# 1-Schematic_TFG-DALI.net
KiCad netlist of a schematic drawn in EasyEDA
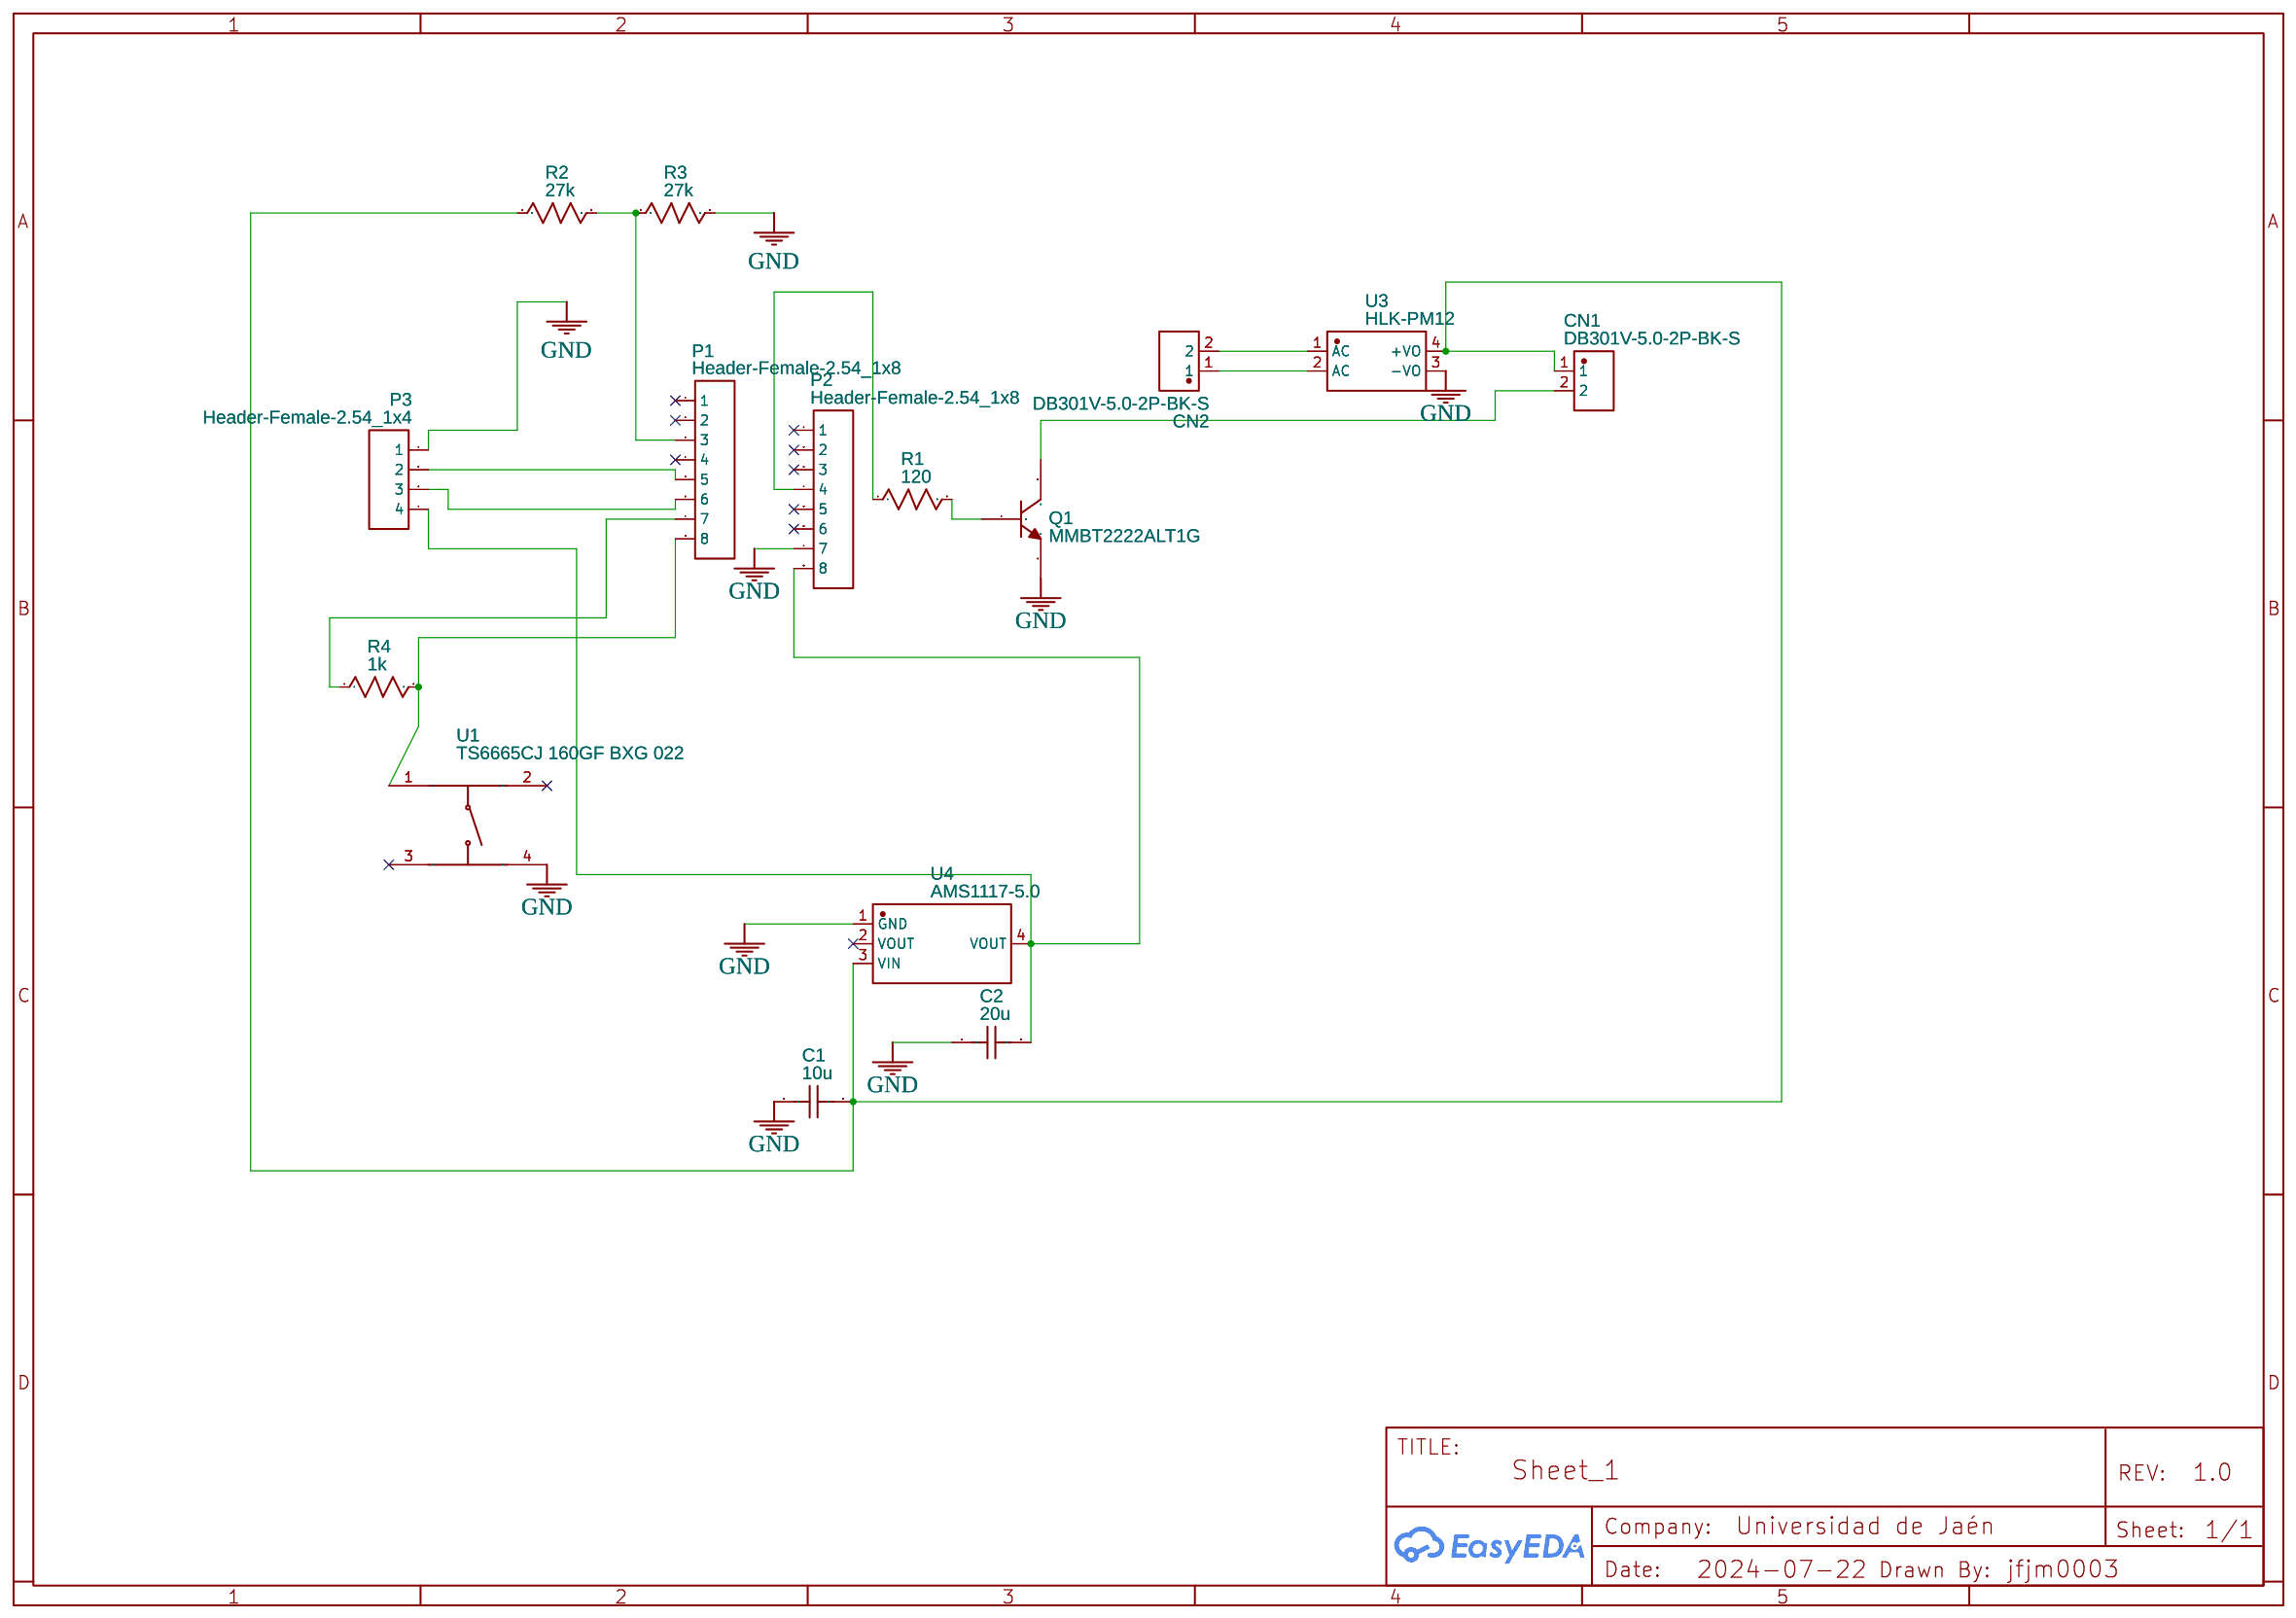
[diagram p0: schematic sheet]

(export (version "E")
  (design (tool "Eeschema 10.0.6"))
  (components
    (comp (ref "C1")
      (value "10u")
      (fields
        (field (name "Manufacturer Part") "CL31A106KBHNNNE")
        (field (name "Manufacturer") "SAMSUNG(三星)")
      )
      (libsource (lib "") (part "C_0603_US"))
    )
    (comp (ref "C2")
      (value "20u")
      (fields
        (field (name "Manufacturer Part") "GRMJN7R61C206ME05D")
        (field (name "Manufacturer") "muRata(村田)")
      )
      (libsource (lib "") (part "C_0603_US"))
    )
    (comp (ref "CN1")
      (value "DB301V-5.0-2P-BK-S")
      (fields (field (name "Manufacturer") "DORABO(地博电气)"))
      (libsource (lib "") (part "DB301V-5.0-2P-BK-S"))
    )
    (comp (ref "CN2")
      (value "DB301V-5.0-2P-BK-S")
      (fields (field (name "Manufacturer") "DORABO(地博电气)"))
      (libsource (lib "") (part "DB301V-5.0-2P-BK-S_1"))
    )
    (comp (ref "P1")
      (value "Header-Female-2.54_1x8")
      (fields (field (name "Manufacturer Part") "2.54-1*8P母环保") (field (name "Manufacturer") "BOOMELE(博穆精密)"))
      (libsource (lib "") (part "Header-Female-2.54_1x8"))
    )
    (comp (ref "P2")
      (value "Header-Female-2.54_1x8")
      (fields (field (name "Manufacturer Part") "2.54-1*8P母环保") (field (name "Manufacturer") "BOOMELE(博穆精密)"))
      (libsource (lib "") (part "Header-Female-2.54_1x8"))
    )
    (comp (ref "P3")
      (value "Header-Female-2.54_1x4")
      (fields (field (name "Manufacturer") "ReliaPro"))
      (libsource (lib "") (part "Header-Female-2.54_1x4"))
    )
    (comp (ref "Q1")
      (value "MMBT2222ALT1G")
      (fields (field (name "Manufacturer") "onsemi(安森美)"))
      (libsource (lib "") (part "MMBT2222ALT1G"))
    )
    (comp (ref "R1") (value "120") (libsource (lib "") (part "R_0603_US")))
    (comp (ref "R2") (value "27k") (libsource (lib "") (part "R_0603_US")))
    (comp (ref "R3") (value "27k") (libsource (lib "") (part "R_0603_US")))
    (comp (ref "R4") (value "1k") (libsource (lib "") (part "R_0603_US")))
    (comp (ref "U1")
      (value "TS6665CJ 160GF BXG 022")
      (fields
        (field (name "Manufacturer Part") "TS6665CJ 160gf BXG 022")
        (field (name "Manufacturer") "SHOU HAN(首韩)")
      )
      (libsource (lib "") (part "TS6665CJ 160GF BXG 022"))
    )
    (comp (ref "U3")
      (value "HLK-PM12")
      (fields (field (name "Manufacturer") "HI-LINK(海凌科)"))
      (libsource (lib "") (part "HLK-PM12"))
    )
    (comp (ref "U4")
      (value "AMS1117-5.0")
      (fields (field (name "Manufacturer") "AMS"))
      (libsource (lib "") (part "AMS1117-5.0"))
    )
  )
  (nets
    (net (code "1") (name "GND") (class "Default")
      (node (ref "C1") (pin "1") (pinfunction "1_1") (pintype "unspecified"))
      (node (ref "C2") (pin "1") (pinfunction "1_1") (pintype "unspecified"))
      (node (ref "P2") (pin "7") (pinfunction "7_7") (pintype "input"))
      (node (ref "P3") (pin "1") (pinfunction "1_1") (pintype "input"))
      (node (ref "Q1") (pin "2") (pinfunction "E_2") (pintype "unspecified"))
      (node (ref "R3") (pin "2") (pinfunction "2_2") (pintype "unspecified"))
      (node (ref "U1") (pin "4") (pinfunction "D_4") (pintype "unspecified"))
      (node (ref "U3") (pin "3") (pinfunction "-VO_3") (pintype "unspecified"))
      (node (ref "U4") (pin "1") (pinfunction "GND_1") (pintype "unspecified"))
    )
    (net (code "2") (name "Net-(C2-Pad2)") (class "Default")
      (node (ref "C2") (pin "2") (pinfunction "2_2") (pintype "unspecified"))
      (node (ref "P2") (pin "8") (pinfunction "8_8") (pintype "input"))
      (node (ref "P3") (pin "4") (pinfunction "4_4") (pintype "input"))
      (node (ref "U4") (pin "4") (pinfunction "VOUT_4") (pintype "unspecified"))
    )
    (net (code "3") (name "Net-(CN2-Pad1)") (class "Default")
      (node (ref "CN2") (pin "1") (pinfunction "1_1") (pintype "unspecified"))
      (node (ref "U3") (pin "2") (pinfunction "AC_2") (pintype "unspecified"))
    )
    (net (code "4") (name "Net-(CN2-Pad2)") (class "Default")
      (node (ref "CN2") (pin "2") (pinfunction "2_2") (pintype "unspecified"))
      (node (ref "U3") (pin "1") (pinfunction "AC_1") (pintype "unspecified"))
    )
    (net (code "5") (name "Net-(P1-Pad3)") (class "Default")
      (node (ref "P1") (pin "3") (pinfunction "3_3") (pintype "input"))
      (node (ref "R2") (pin "2") (pinfunction "2_2") (pintype "unspecified"))
      (node (ref "R3") (pin "1") (pinfunction "1_1") (pintype "unspecified"))
    )
    (net (code "6") (name "Net-(P1-Pad5)") (class "Default")
      (node (ref "P1") (pin "5") (pinfunction "5_5") (pintype "input"))
      (node (ref "P3") (pin "2") (pinfunction "2_2") (pintype "input"))
    )
    (net (code "7") (name "Net-(P1-Pad6)") (class "Default")
      (node (ref "P1") (pin "6") (pinfunction "6_6") (pintype "input"))
      (node (ref "P3") (pin "3") (pinfunction "3_3") (pintype "input"))
    )
    (net (code "8") (name "Net-(P1-Pad7)") (class "Default")
      (node (ref "P1") (pin "7") (pinfunction "7_7") (pintype "input"))
      (node (ref "R4") (pin "1") (pinfunction "1_1") (pintype "unspecified"))
    )
    (net (code "9") (name "Net-(P2-Pad4)") (class "Default")
      (node (ref "P2") (pin "4") (pinfunction "4_4") (pintype "input"))
      (node (ref "R1") (pin "1") (pinfunction "1_1") (pintype "unspecified"))
    )
    (net (code "10") (name "Net-(Q1-B)") (class "Default")
      (node (ref "Q1") (pin "1") (pinfunction "B_1") (pintype "unspecified"))
      (node (ref "R1") (pin "2") (pinfunction "2_2") (pintype "unspecified"))
    )
    (net (code "11") (name "Net-(Q1-C)") (class "Default")
      (node (ref "CN1") (pin "2") (pinfunction "2_2") (pintype "unspecified"))
      (node (ref "Q1") (pin "3") (pinfunction "C_3") (pintype "unspecified"))
    )
    (net (code "12") (name "Net-(U1-A)") (class "Default")
      (node (ref "P1") (pin "8") (pinfunction "8_8") (pintype "input"))
      (node (ref "R4") (pin "2") (pinfunction "2_2") (pintype "unspecified"))
      (node (ref "U1") (pin "1") (pinfunction "A_1") (pintype "unspecified"))
    )
    (net (code "13") (name "Net-(U3-+VO)") (class "Default")
      (node (ref "C1") (pin "2") (pinfunction "2_2") (pintype "unspecified"))
      (node (ref "CN1") (pin "1") (pinfunction "1_1") (pintype "unspecified"))
      (node (ref "R2") (pin "1") (pinfunction "1_1") (pintype "unspecified"))
      (node (ref "U3") (pin "4") (pinfunction "+VO_4") (pintype "unspecified"))
      (node (ref "U4") (pin "3") (pinfunction "VIN_3") (pintype "unspecified"))
    )
    (net (code "14") (name "unconnected-(P1-Pad1)") (class "Default")
      (node (ref "P1") (pin "1") (pinfunction "1_1") (pintype "input+no_connect"))
    )
    (net (code "15") (name "unconnected-(P1-Pad2)") (class "Default")
      (node (ref "P1") (pin "2") (pinfunction "2_2") (pintype "input+no_connect"))
    )
    (net (code "16") (name "unconnected-(P1-Pad4)") (class "Default")
      (node (ref "P1") (pin "4") (pinfunction "4_4") (pintype "input+no_connect"))
    )
    (net (code "17") (name "unconnected-(P2-Pad1)") (class "Default")
      (node (ref "P2") (pin "1") (pinfunction "1_1") (pintype "input+no_connect"))
    )
    (net (code "18") (name "unconnected-(P2-Pad2)") (class "Default")
      (node (ref "P2") (pin "2") (pinfunction "2_2") (pintype "input+no_connect"))
    )
    (net (code "19") (name "unconnected-(P2-Pad3)") (class "Default")
      (node (ref "P2") (pin "3") (pinfunction "3_3") (pintype "input+no_connect"))
    )
    (net (code "20") (name "unconnected-(P2-Pad5)") (class "Default")
      (node (ref "P2") (pin "5") (pinfunction "5_5") (pintype "input+no_connect"))
    )
    (net (code "21") (name "unconnected-(P2-Pad6)") (class "Default")
      (node (ref "P2") (pin "6") (pinfunction "6_6") (pintype "input+no_connect"))
    )
    (net (code "22") (name "unconnected-(U1-B-Pad2)") (class "Default")
      (node (ref "U1") (pin "2") (pinfunction "B_2") (pintype "unspecified+no_connect"))
    )
    (net (code "23") (name "unconnected-(U1-C-Pad3)") (class "Default")
      (node (ref "U1") (pin "3") (pinfunction "C_3") (pintype "unspecified+no_connect"))
    )
    (net (code "24") (name "unconnected-(U4-VOUT-Pad2)") (class "Default")
      (node (ref "U4") (pin "2") (pinfunction "VOUT_2") (pintype "unspecified+no_connect"))
    )
  )
)
